# power.net
KiCad netlist of a schematic drawn in Altium Designer
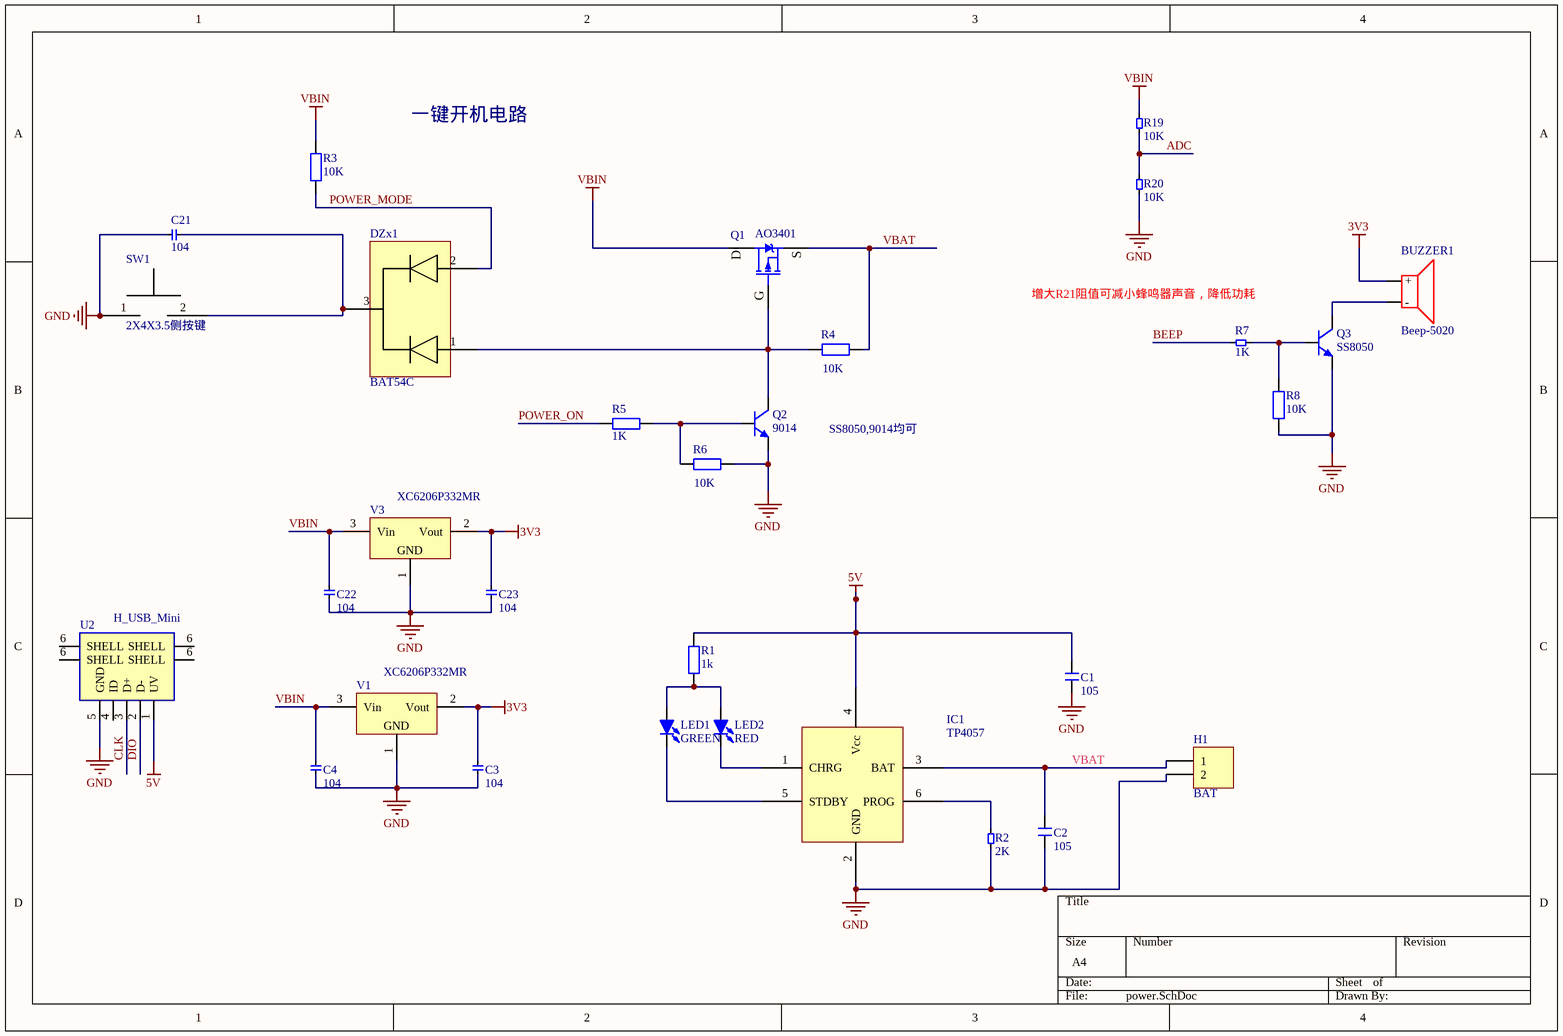
[diagram p0: power.SchDoc]

(export (version "E")
  (design (tool "Eeschema 10.0.6"))
  (components
    (comp (ref "BUZZER1")
      (value "Beep-5020")
      (footprint "5020BUZZER")
      (description "贴片蜂鸣器5020最小封装")
      (libsource (lib "我的元件") (part "Beep-5020"))
    )
    (comp (ref "C1")
      (value "105")
      (footprint "C0603")
      (description "无极性贴片电容")
      (fields (field (name "版权归属") "源创客"))
      (libsource (lib "3.1   - 电阻-电容-电感") (part "C"))
    )
    (comp (ref "C2")
      (value "105")
      (footprint "C0603")
      (description "无极性贴片电容")
      (fields (field (name "版权归属") "源创客"))
      (libsource (lib "3.1   - 电阻-电容-电感") (part "C"))
    )
    (comp (ref "C3")
      (value "104")
      (footprint "C_0603")
      (description "无极性贴片电容")
      (libsource (lib "电阻电容电感库") (part "C_无极贴片"))
    )
    (comp (ref "C4")
      (value "104")
      (footprint "C_0603")
      (description "无极性贴片电容")
      (libsource (lib "电阻电容电感库") (part "C_无极贴片"))
    )
    (comp (ref "C21")
      (value "104")
      (footprint "C_0603")
      (description "无极性贴片电容")
      (libsource (lib "电阻电容电感库") (part "C_无极贴片"))
    )
    (comp (ref "C22")
      (value "104")
      (footprint "C_0603")
      (description "无极性贴片电容")
      (libsource (lib "电阻电容电感库") (part "C_无极贴片"))
    )
    (comp (ref "C23")
      (value "104")
      (footprint "C_0603")
      (description "无极性贴片电容")
      (libsource (lib "电阻电容电感库") (part "C_无极贴片"))
    )
    (comp (ref "DZx1")
      (value "BAT54C")
      (footprint "SOT23-3N")
      (description "双肖特基，共阴极")
      (libsource (lib "我的元件") (part "BAT54C"))
    )
    (comp (ref "H1")
      (value "BAT")
      (footprint "H_Header_1X2")
      (description "单排2针排母")
      (fields (field (name "PUBLISHER") "Altium Limited"))
      (libsource (lib "接插件") (part "H_Header_1X2H"))
    )
    (comp (ref "IC1")
      (value "TP4057")
      (footprint "SOT23-6N")
      (description "500mA/600mA锂电池充电管理IC")
      (libsource (lib "1.3   - 电源类芯片") (part "TP4057/4059"))
    )
    (comp (ref "LED1")
      (value "GREEN")
      (footprint "D0603G")
      (description "贴片LED")
      (fields (field (name "版权归属") "源创客"))
      (libsource (lib "9.1   - LED") (part "LED-SMD"))
    )
    (comp (ref "LED2")
      (value "RED")
      (footprint "D0603R")
      (description "贴片LED")
      (fields (field (name "版权归属") "源创客"))
      (libsource (lib "9.1   - LED") (part "LED-SMD"))
    )
    (comp (ref "Q1")
      (value "AO3401")
      (footprint "SOT23-3N")
      (description "P沟道场效应管")
      (fields (field (name "版权归属") "源创客"))
      (libsource (lib "6.1   - 场效应管-可控硅") (part "SI2301"))
    )
    (comp (ref "Q2")
      (value "9014")
      (footprint "SOT23-3N")
      (description "低噪放大-NPN型")
      (fields (field (name "版权归属") "源创客"))
      (libsource (lib "6.2   - 三极管") (part "9014-SMD"))
    )
    (comp (ref "Q3")
      (value "SS8050")
      (footprint "SOT23-3N")
      (description "高频放大-NPN型")
      (fields (field (name "版权归属") "源创客"))
      (libsource (lib "6.2   - 三极管") (part "8050-SMD"))
    )
    (comp (ref "R1")
      (value "1k")
      (footprint "R0603")
      (description "贴片电阻")
      (fields (field (name "版权归属") "源创客"))
      (libsource (lib "3.1   - 电阻-电容-电感") (part "R"))
    )
    (comp (ref "R2")
      (value "2K")
      (footprint "R_0603")
      (description "贴片电阻")
      (libsource (lib "电阻电容电感库") (part "R_贴片"))
    )
    (comp (ref "R3")
      (value "10K")
      (footprint "R0603")
      (description "贴片电阻")
      (fields (field (name "版权归属") "源创客"))
      (libsource (lib "3.1   - 电阻-电容-电感") (part "R"))
    )
    (comp (ref "R4")
      (value "10K")
      (footprint "R0603")
      (description "贴片电阻")
      (fields (field (name "版权归属") "源创客"))
      (libsource (lib "3.1   - 电阻-电容-电感") (part "R"))
    )
    (comp (ref "R5")
      (value "1K")
      (footprint "R0603")
      (description "贴片电阻")
      (fields (field (name "版权归属") "源创客"))
      (libsource (lib "3.1   - 电阻-电容-电感") (part "R"))
    )
    (comp (ref "R6")
      (value "10K")
      (footprint "R0603")
      (description "贴片电阻")
      (fields (field (name "版权归属") "源创客"))
      (libsource (lib "3.1   - 电阻-电容-电感") (part "R"))
    )
    (comp (ref "R7")
      (value "1K")
      (footprint "R_0603")
      (description "贴片电阻")
      (libsource (lib "电阻电容电感库") (part "R_贴片"))
    )
    (comp (ref "R8")
      (value "10K")
      (footprint "R0603")
      (description "贴片电阻")
      (fields (field (name "版权归属") "源创客"))
      (libsource (lib "3.1   - 电阻-电容-电感") (part "R"))
    )
    (comp (ref "R19")
      (value "10K")
      (footprint "R_0603")
      (description "贴片电阻")
      (libsource (lib "电阻电容电感库") (part "R_贴片"))
    )
    (comp (ref "R20")
      (value "10K")
      (footprint "R_0603")
      (description "贴片电阻")
      (libsource (lib "电阻电容电感库") (part "R_贴片"))
    )
    (comp (ref "SW1")
      (value "2X4X3.5侧按键")
      (footprint "2X4X3.5贴片侧按开关")
      (libsource (lib "MyWatch") (part "2X4X3.5侧按键"))
    )
    (comp (ref "U2")
      (value "H_USB_Mini")
      (footprint "H_USB_Mini_A")
      (description "MiniUSB头母头")
      (libsource (lib "接插件") (part "H_USB_Mini"))
    )
    (comp (ref "V1")
      (value "XC6206P332MR")
      (footprint "SOT23-3N")
      (description "低压差线性稳压芯片")
      (fields (field (name "版权归属") "源创客"))
      (libsource (lib "MyWatch") (part "XC6206P332MR"))
    )
    (comp (ref "V3")
      (value "XC6206P332MR")
      (footprint "SOT23-3N")
      (description "低压差线性稳压芯片")
      (fields (field (name "版权归属") "源创客"))
      (libsource (lib "MyWatch") (part "XC6206P332MR"))
    )
  )
  (nets
    (net (code "1") (name "/ADC") (class "Default")
      (node (ref "R19") (pin "2") (pintype "passive"))
      (node (ref "R20") (pin "1") (pintype "passive"))
    )
    (net (code "2") (name "/BEEP") (class "Default") (node (ref "R7") (pin "1") (pintype "passive")))
    (net (code "3") (name "/CLK") (class "Default")
      (node (ref "U2") (pin "3") (pinfunction "D+_3") (pintype "passive"))
    )
    (net (code "4") (name "/DIO") (class "Default")
      (node (ref "U2") (pin "2") (pinfunction "D-_2") (pintype "passive"))
    )
    (net (code "5") (name "/POWER_MODE") (class "Default")
      (node (ref "DZx1") (pin "2") (pinfunction "2_2") (pintype "passive"))
      (node (ref "R3") (pin "1") (pinfunction "1_1") (pintype "passive"))
    )
    (net (code "6") (name "/POWER_ON") (class "Default")
      (node (ref "R5") (pin "1") (pinfunction "1_1") (pintype "passive"))
    )
    (net (code "7") (name "/VBAT") (class "Default")
      (node (ref "C2") (pin "2") (pinfunction "2_2") (pintype "passive"))
      (node (ref "H1") (pin "1") (pinfunction "1_1") (pintype "passive"))
      (node (ref "IC1") (pin "3") (pinfunction "BAT_3") (pintype "passive"))
      (node (ref "Q1") (pin "2") (pinfunction "S_2") (pintype "passive"))
      (node (ref "R4") (pin "2") (pinfunction "2_2") (pintype "passive"))
    )
    (net (code "8") (name "3V3") (class "Default")
      (node (ref "BUZZER1") (pin "1") (pinfunction "+_1") (pintype "passive"))
      (node (ref "C23") (pin "2") (pinfunction "2_2") (pintype "passive"))
      (node (ref "C3") (pin "2") (pinfunction "2_2") (pintype "passive"))
      (node (ref "V1") (pin "2") (pinfunction "Vout_2") (pintype "passive"))
      (node (ref "V3") (pin "2") (pinfunction "Vout_2") (pintype "passive"))
    )
    (net (code "9") (name "5V") (class "Default")
      (node (ref "C1") (pin "2") (pinfunction "2_2") (pintype "passive"))
      (node (ref "IC1") (pin "4") (pinfunction "Vcc_4") (pintype "passive"))
      (node (ref "R1") (pin "2") (pinfunction "2_2") (pintype "passive"))
      (node (ref "U2") (pin "1") (pinfunction "UV_1") (pintype "passive"))
    )
    (net (code "10") (name "GND") (class "Default")
      (node (ref "C1") (pin "1") (pinfunction "1_1") (pintype "passive"))
      (node (ref "C2") (pin "1") (pinfunction "1_1") (pintype "passive"))
      (node (ref "C21") (pin "1") (pinfunction "1_1") (pintype "passive"))
      (node (ref "C22") (pin "1") (pinfunction "1_1") (pintype "passive"))
      (node (ref "C23") (pin "1") (pinfunction "1_1") (pintype "passive"))
      (node (ref "C3") (pin "1") (pinfunction "1_1") (pintype "passive"))
      (node (ref "C4") (pin "1") (pinfunction "1_1") (pintype "passive"))
      (node (ref "H1") (pin "2") (pinfunction "2_2") (pintype "passive"))
      (node (ref "IC1") (pin "2") (pinfunction "GND_2") (pintype "passive"))
      (node (ref "Q2") (pin "2") (pinfunction "E_2") (pintype "passive"))
      (node (ref "Q3") (pin "2") (pinfunction "E_2") (pintype "passive"))
      (node (ref "R2") (pin "1") (pintype "passive"))
      (node (ref "R20") (pin "2") (pintype "passive"))
      (node (ref "R6") (pin "2") (pinfunction "2_2") (pintype "passive"))
      (node (ref "R8") (pin "1") (pinfunction "1_1") (pintype "passive"))
      (node (ref "SW1") (pin "1") (pinfunction "1_1") (pintype "passive"))
      (node (ref "U2") (pin "5") (pinfunction "GND_5") (pintype "passive"))
      (node (ref "V1") (pin "1") (pinfunction "GND_1") (pintype "passive"))
      (node (ref "V3") (pin "1") (pinfunction "GND_1") (pintype "passive"))
    )
    (net (code "11") (name "Net-(BUZZER1--)") (class "Default")
      (node (ref "BUZZER1") (pin "2") (pinfunction "-_2") (pintype "passive"))
      (node (ref "Q3") (pin "3") (pinfunction "C_3") (pintype "passive"))
    )
    (net (code "12") (name "Net-(C21-Pad2)") (class "Default")
      (node (ref "C21") (pin "2") (pinfunction "2_2") (pintype "passive"))
      (node (ref "DZx1") (pin "3") (pinfunction "3_3") (pintype "passive"))
      (node (ref "SW1") (pin "2") (pinfunction "2_2") (pintype "passive"))
    )
    (net (code "13") (name "Net-(IC1-CHRG)") (class "Default")
      (node (ref "IC1") (pin "1") (pinfunction "CHRG_1") (pintype "passive"))
      (node (ref "LED2") (pin "2") (pinfunction "K_2") (pintype "passive"))
    )
    (net (code "14") (name "Net-(IC1-PROG)") (class "Default")
      (node (ref "IC1") (pin "6") (pinfunction "PROG_6") (pintype "passive"))
      (node (ref "R2") (pin "2") (pintype "passive"))
    )
    (net (code "15") (name "Net-(IC1-STDBY)") (class "Default")
      (node (ref "IC1") (pin "5") (pinfunction "STDBY_5") (pintype "passive"))
      (node (ref "LED1") (pin "2") (pinfunction "K_2") (pintype "passive"))
    )
    (net (code "16") (name "Net-(LED1-A)") (class "Default")
      (node (ref "LED1") (pin "1") (pinfunction "A_1") (pintype "passive"))
      (node (ref "LED2") (pin "1") (pinfunction "A_1") (pintype "passive"))
      (node (ref "R1") (pin "1") (pinfunction "1_1") (pintype "passive"))
    )
    (net (code "17") (name "Net-(Q1-G)") (class "Default")
      (node (ref "DZx1") (pin "1") (pinfunction "1_1") (pintype "passive"))
      (node (ref "Q1") (pin "1") (pinfunction "G_1") (pintype "passive"))
      (node (ref "Q2") (pin "3") (pinfunction "C_3") (pintype "passive"))
      (node (ref "R4") (pin "1") (pinfunction "1_1") (pintype "passive"))
    )
    (net (code "18") (name "Net-(Q2-B)") (class "Default")
      (node (ref "Q2") (pin "1") (pinfunction "B_1") (pintype "passive"))
      (node (ref "R5") (pin "2") (pinfunction "2_2") (pintype "passive"))
      (node (ref "R6") (pin "1") (pinfunction "1_1") (pintype "passive"))
    )
    (net (code "19") (name "Net-(Q3-B)") (class "Default")
      (node (ref "Q3") (pin "1") (pinfunction "B_1") (pintype "passive"))
      (node (ref "R7") (pin "2") (pintype "passive"))
      (node (ref "R8") (pin "2") (pinfunction "2_2") (pintype "passive"))
    )
    (net (code "20") (name "VBIN") (class "Default")
      (node (ref "C22") (pin "2") (pinfunction "2_2") (pintype "passive"))
      (node (ref "C4") (pin "2") (pinfunction "2_2") (pintype "passive"))
      (node (ref "Q1") (pin "3") (pinfunction "D_3") (pintype "passive"))
      (node (ref "R19") (pin "1") (pintype "passive"))
      (node (ref "R3") (pin "2") (pinfunction "2_2") (pintype "passive"))
      (node (ref "V1") (pin "3") (pinfunction "Vin_3") (pintype "passive"))
      (node (ref "V3") (pin "3") (pinfunction "Vin_3") (pintype "passive"))
    )
    (net (code "21") (name "unconnected-(U2-ID-Pad4)") (class "Default")
      (node (ref "U2") (pin "4") (pinfunction "ID_4") (pintype "passive"))
    )
    (net (code "22") (name "unconnected-(U2-SHELL-Pad6)") (class "Default")
      (node (ref "U2") (pin "6") (pinfunction "SHELL_6") (pintype "passive"))
    )
    (net (code "23") (name "unconnected-(U2-SHELL-Pad6)_1") (class "Default")
      (node (ref "U2") (pin "6") (pinfunction "SHELL_6") (pintype "passive"))
    )
    (net (code "24") (name "unconnected-(U2-SHELL-Pad6)_2") (class "Default")
      (node (ref "U2") (pin "6") (pinfunction "SHELL_6") (pintype "passive"))
    )
    (net (code "25") (name "unconnected-(U2-SHELL-Pad6)_3") (class "Default")
      (node (ref "U2") (pin "6") (pinfunction "SHELL_6") (pintype "passive"))
    )
  )
)
